# 12_BCKPLN_FPGA_J008340C.net
KiCad netlist of a schematic drawn in EAGLE
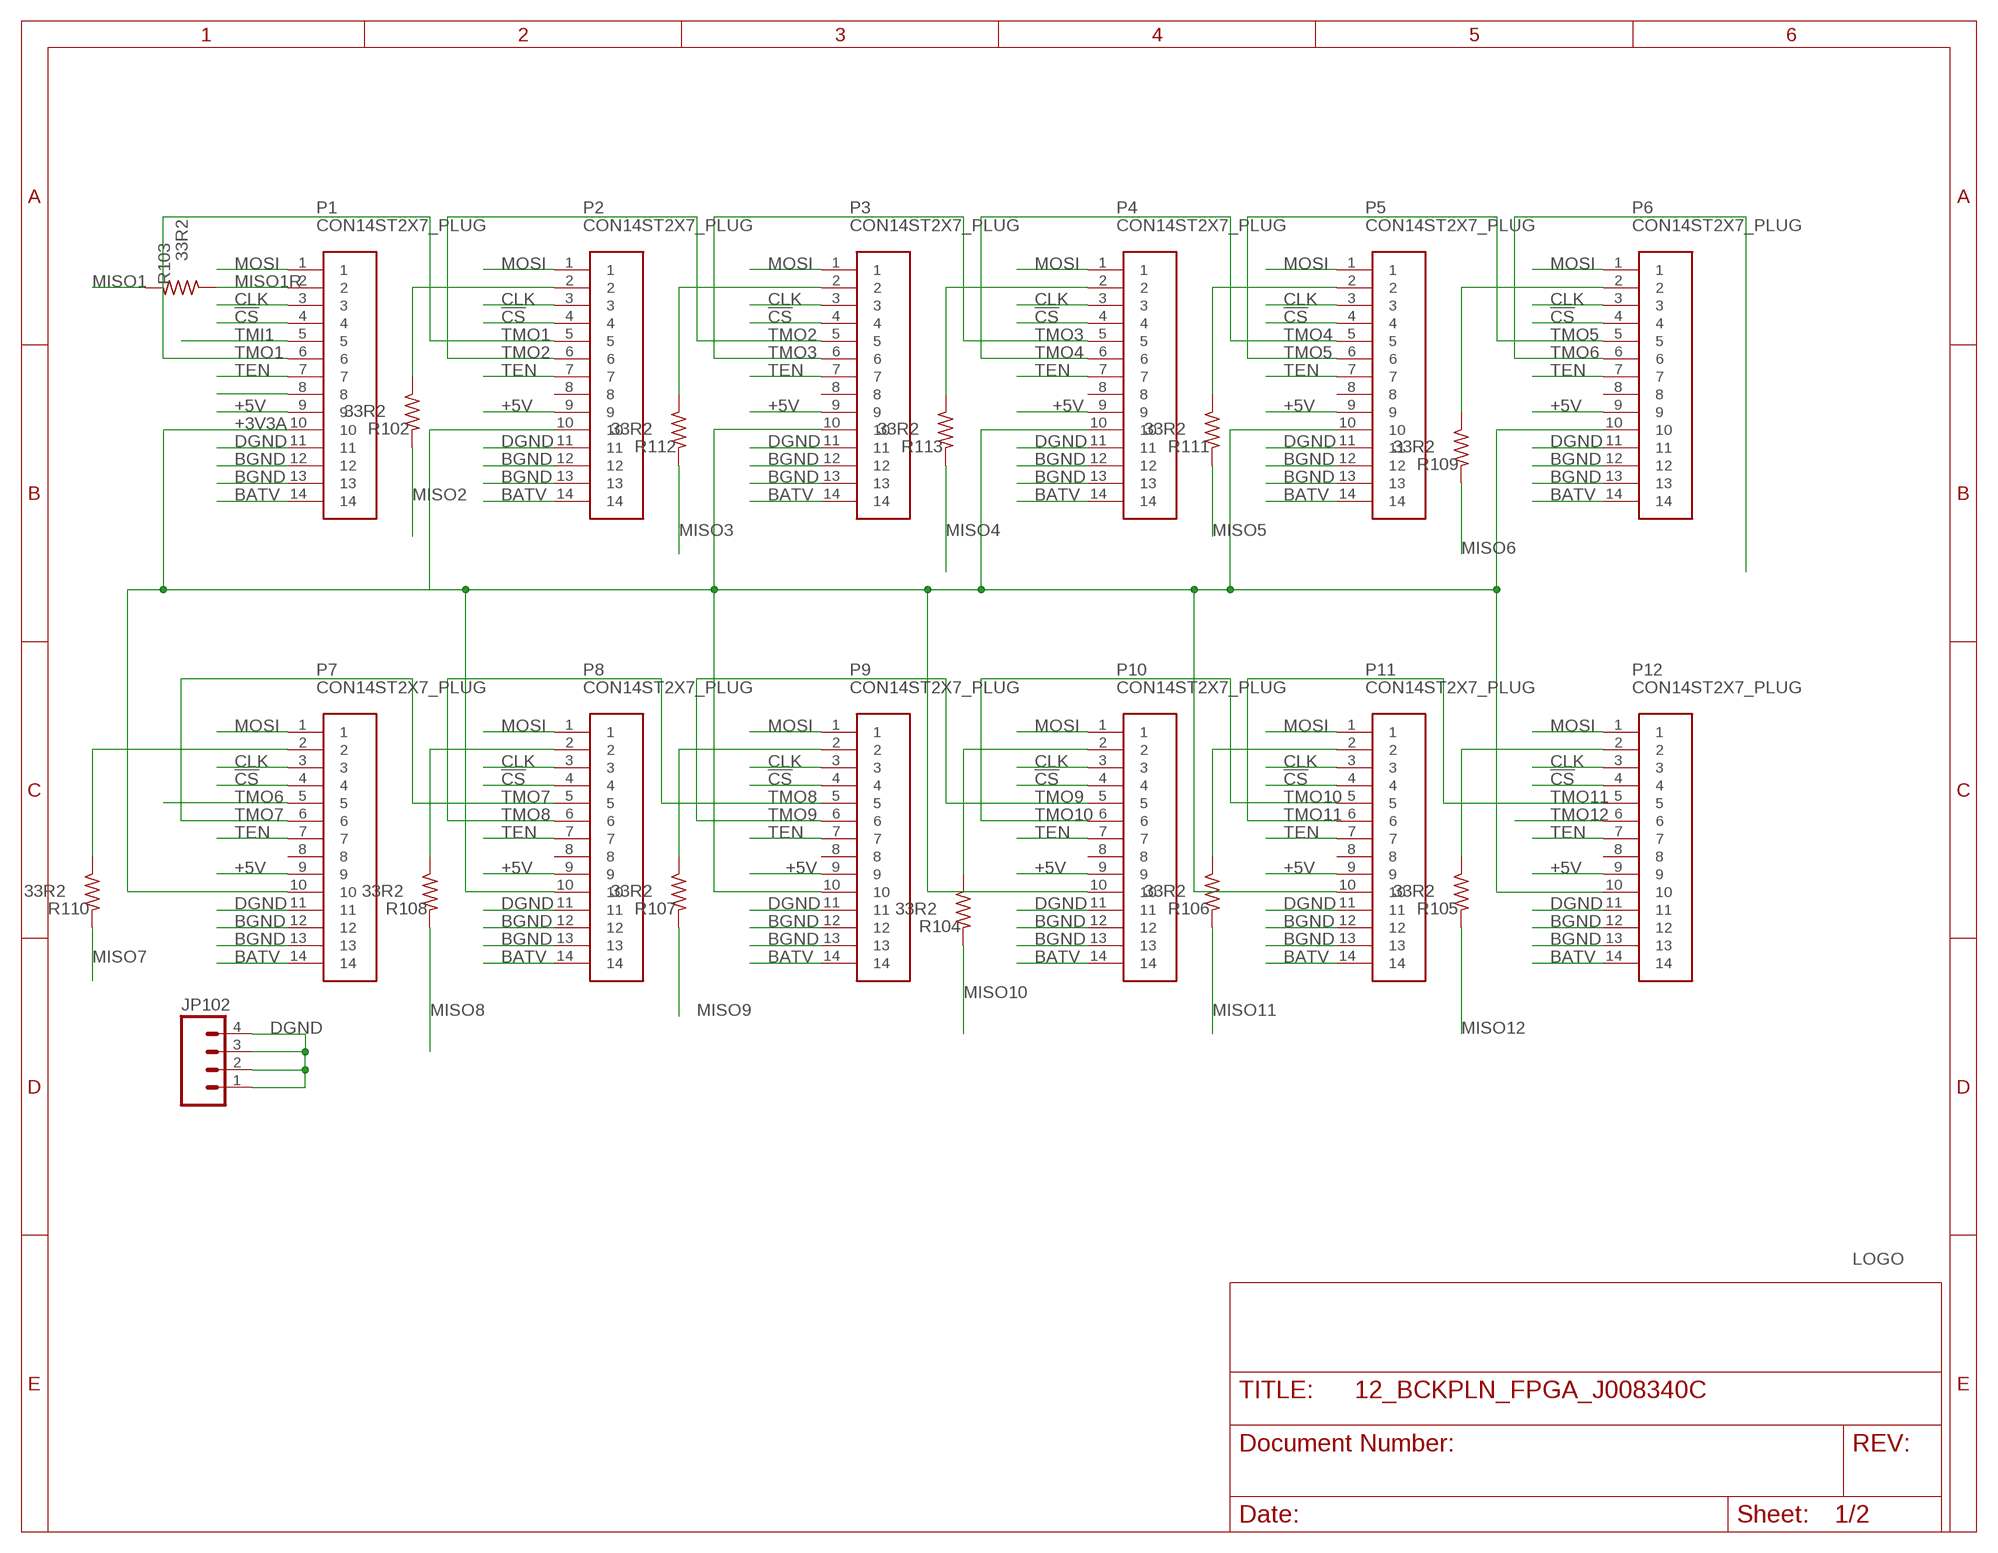
[diagram p0: schematic, sheet 1]
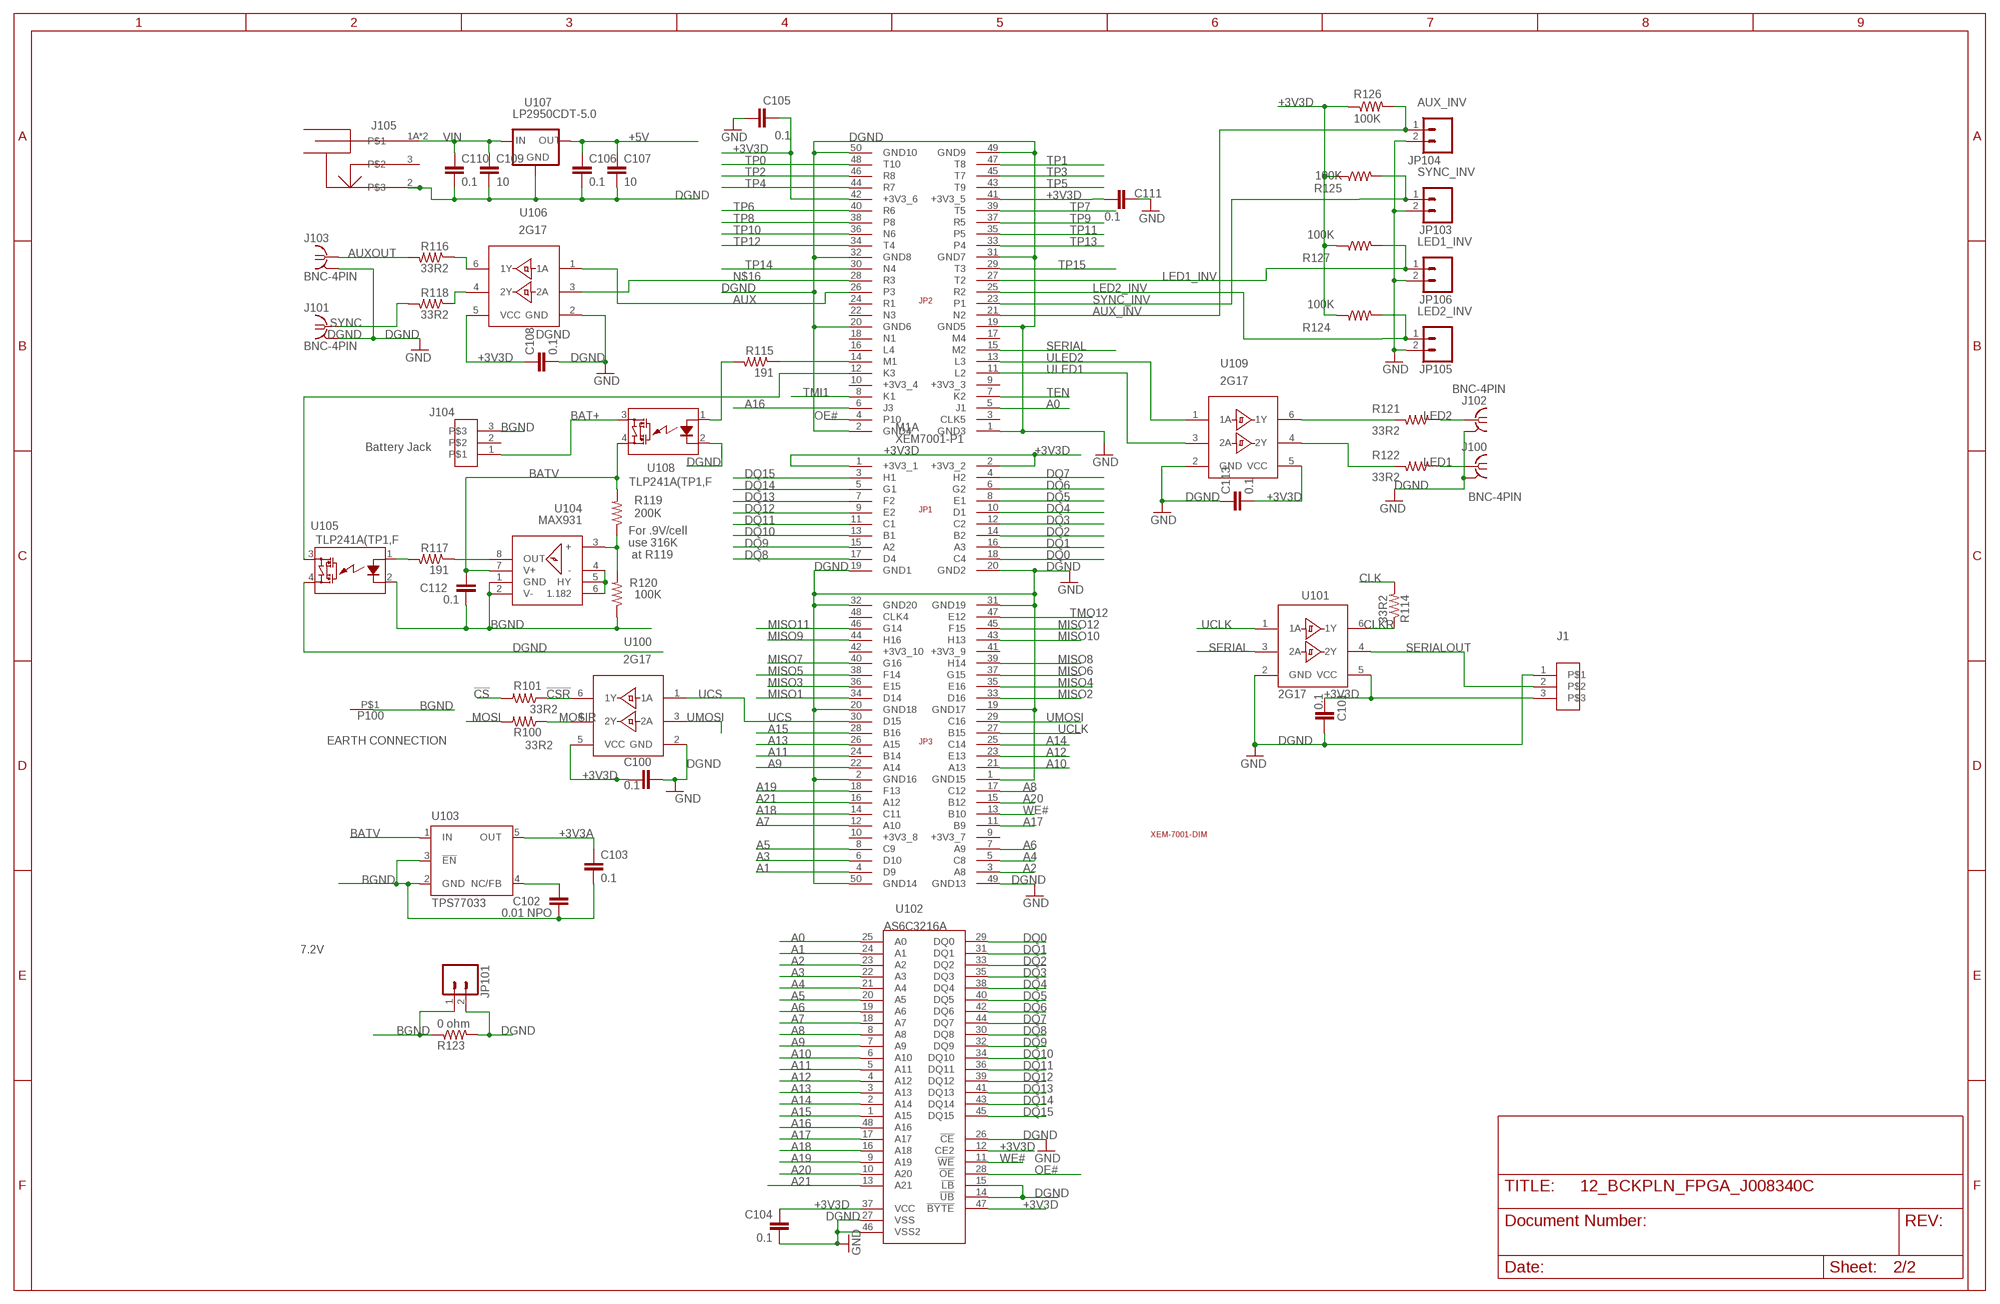
[diagram p1: schematic, sheet 2]

(export (version "E")
  (design (tool "Eeschema 10.0.6"))
  (components
    (comp (ref "C100")
      (value "0.1")
      (footprint "eagle-import:0603S")
      (libsource (lib "eagle-import") (part "CAPS0603S"))
    )
    (comp (ref "C101")
      (value "0.1")
      (footprint "eagle-import:0603S")
      (libsource (lib "eagle-import") (part "CAPS0603S"))
    )
    (comp (ref "C102")
      (value "0.01 NPO")
      (footprint "eagle-import:0805S")
      (libsource (lib "eagle-import") (part "CAPS0805S"))
    )
    (comp (ref "C103")
      (value "0.1")
      (footprint "eagle-import:0603S")
      (libsource (lib "eagle-import") (part "CAPS0603S"))
    )
    (comp (ref "C104")
      (value "0.1")
      (footprint "eagle-import:0603S")
      (libsource (lib "eagle-import") (part "CAPS0603S"))
    )
    (comp (ref "C105")
      (value "0.1")
      (footprint "eagle-import:0603S")
      (libsource (lib "eagle-import") (part "CAPS0603S"))
    )
    (comp (ref "C106")
      (value "0.1")
      (footprint "eagle-import:0603S")
      (libsource (lib "eagle-import") (part "CAPS0603S"))
    )
    (comp (ref "C107")
      (value "10")
      (footprint "eagle-import:1210S")
      (libsource (lib "eagle-import") (part "CAPS1210S"))
    )
    (comp (ref "C108")
      (value "0.1")
      (footprint "eagle-import:0603S")
      (libsource (lib "eagle-import") (part "CAPS0603S"))
    )
    (comp (ref "C109")
      (value "10")
      (footprint "eagle-import:1210S")
      (libsource (lib "eagle-import") (part "CAPS1210S"))
    )
    (comp (ref "C110")
      (value "0.1")
      (footprint "eagle-import:0603S")
      (libsource (lib "eagle-import") (part "CAPS0603S"))
    )
    (comp (ref "C111")
      (value "0.1")
      (footprint "eagle-import:0603S")
      (libsource (lib "eagle-import") (part "CAPS0603S"))
    )
    (comp (ref "C112")
      (value "0.1")
      (footprint "eagle-import:0603S")
      (libsource (lib "eagle-import") (part "CAPS0603S"))
    )
    (comp (ref "C113")
      (value "0.1")
      (footprint "eagle-import:0603S")
      (libsource (lib "eagle-import") (part "CAPS0603S"))
    )
    (comp (ref "J1")
      (value "CON3AMPMODU-3")
      (footprint "eagle-import:AMPMODU-3")
      (libsource (lib "eagle-import") (part "CON3AMPMODU-3"))
    )
    (comp (ref "J100")
      (value "BNC-4PIN")
      (footprint "eagle-import:BNC-4PIN")
      (libsource (lib "eagle-import") (part "BNCBNC-4PIN"))
    )
    (comp (ref "J101")
      (value "BNC-4PIN")
      (footprint "eagle-import:BNC-4PIN")
      (libsource (lib "eagle-import") (part "BNCBNC-4PIN"))
    )
    (comp (ref "J102")
      (value "BNC-4PIN")
      (footprint "eagle-import:BNC-4PIN")
      (libsource (lib "eagle-import") (part "BNCBNC-4PIN"))
    )
    (comp (ref "J103")
      (value "BNC-4PIN")
      (footprint "eagle-import:BNC-4PIN")
      (libsource (lib "eagle-import") (part "BNCBNC-4PIN"))
    )
    (comp (ref "J104")
      (value "Battery Jack")
      (footprint "eagle-import:975")
      (libsource (lib "eagle-import") (part "CON3975"))
    )
    (comp (ref "J105")
      (value "POWER_JACK_SHUNTPJ-002")
      (footprint "eagle-import:PJ-002")
      (libsource (lib "eagle-import") (part "POWER_JACK_SHUNTPJ-002"))
    )
    (comp (ref "JP101")
      (value "M02LOCK")
      (footprint "eagle-import:1X02_LOCK")
      (libsource (lib "eagle-import") (part "M02LOCK"))
    )
    (comp (ref "JP103")
      (value "M02LOCK")
      (footprint "eagle-import:1X02_LOCK")
      (libsource (lib "eagle-import") (part "M02LOCK"))
    )
    (comp (ref "JP104")
      (value "M02LOCK")
      (footprint "eagle-import:1X02_LOCK")
      (libsource (lib "eagle-import") (part "M02LOCK"))
    )
    (comp (ref "JP105")
      (value "M02LOCK")
      (footprint "eagle-import:1X02_LOCK")
      (libsource (lib "eagle-import") (part "M02LOCK"))
    )
    (comp (ref "JP106")
      (value "M02LOCK")
      (footprint "eagle-import:1X02_LOCK")
      (libsource (lib "eagle-import") (part "M02LOCK"))
    )
    (comp (ref "M1")
      (value "XEM7001-OUTLINE")
      (footprint "eagle-import:XEM7001-OUTLINE")
      (libsource (lib "eagle-import") (part "XEM7001-OUTLINE"))
    )
    (comp (ref "M1A")
      (value "XEM7001-P1")
      (footprint "eagle-import:2X10")
      (libsource (lib "eagle-import") (part "XEM7001-P1"))
    )
    (comp (ref "M1B")
      (value "XEM7001-P2")
      (footprint "eagle-import:2X25")
      (libsource (lib "eagle-import") (part "XEM7001-P2"))
    )
    (comp (ref "M1C")
      (value "XEM7001-P3")
      (footprint "eagle-import:2X25")
      (libsource (lib "eagle-import") (part "XEM7001-P3"))
    )
    (comp (ref "P100")
      (value "CON1BANANA-1")
      (footprint "eagle-import:BANANA-1")
      (libsource (lib "eagle-import") (part "CON1BANANA-1"))
    )
    (comp (ref "R100")
      (value "33R2")
      (footprint "eagle-import:0805S")
      (libsource (lib "eagle-import") (part "STEVES_BU_RESISTOR_SM0805S"))
    )
    (comp (ref "R101")
      (value "33R2")
      (footprint "eagle-import:0805S")
      (libsource (lib "eagle-import") (part "STEVES_BU_RESISTOR_SM0805S"))
    )
    (comp (ref "R114")
      (value "33R2")
      (footprint "eagle-import:0805S")
      (libsource (lib "eagle-import") (part "STEVES_BU_RESISTOR_SM0805S"))
    )
    (comp (ref "R115")
      (value "191")
      (footprint "eagle-import:0805S")
      (libsource (lib "eagle-import") (part "STEVES_BU_RESISTOR_SM0805S"))
    )
    (comp (ref "R116")
      (value "33R2")
      (footprint "eagle-import:0805S")
      (libsource (lib "eagle-import") (part "RESISTOR_SM0805S"))
    )
    (comp (ref "R117")
      (value "191")
      (footprint "eagle-import:0805S")
      (libsource (lib "eagle-import") (part "STEVES_BU_RESISTOR_SM0805S"))
    )
    (comp (ref "R118")
      (value "33R2")
      (footprint "eagle-import:0805S")
      (libsource (lib "eagle-import") (part "RESISTOR_SM0805S"))
    )
    (comp (ref "R119")
      (value "200K")
      (footprint "eagle-import:0805S")
      (libsource (lib "eagle-import") (part "STEVES_BU_RESISTOR_SM0805S"))
    )
    (comp (ref "R120")
      (value "100K")
      (footprint "eagle-import:0805S")
      (libsource (lib "eagle-import") (part "STEVES_BU_RESISTOR_SM0805S"))
    )
    (comp (ref "R121")
      (value "33R2")
      (footprint "eagle-import:0805S")
      (libsource (lib "eagle-import") (part "RESISTOR_SM0805S"))
    )
    (comp (ref "R122")
      (value "33R2")
      (footprint "eagle-import:0805S")
      (libsource (lib "eagle-import") (part "RESISTOR_SM0805S"))
    )
    (comp (ref "R123")
      (value "0 ohm")
      (footprint "eagle-import:0805S")
      (libsource (lib "eagle-import") (part "STEVES_BU_RESISTOR_SM0805S"))
    )
    (comp (ref "R124")
      (value "100K")
      (footprint "eagle-import:0805S")
      (libsource (lib "eagle-import") (part "STEVES_BU_RESISTOR_SM0805S"))
    )
    (comp (ref "R125")
      (value "100K")
      (footprint "eagle-import:0805S")
      (libsource (lib "eagle-import") (part "STEVES_BU_RESISTOR_SM0805S"))
    )
    (comp (ref "R126")
      (value "100K")
      (footprint "eagle-import:0805S")
      (libsource (lib "eagle-import") (part "STEVES_BU_RESISTOR_SM0805S"))
    )
    (comp (ref "R127")
      (value "100K")
      (footprint "eagle-import:0805S")
      (libsource (lib "eagle-import") (part "STEVES_BU_RESISTOR_SM0805S"))
    )
    (comp (ref "U100")
      (value "2G17")
      (footprint "eagle-import:SOT23-6")
      (libsource (lib "eagle-import") (part "2G17"))
    )
    (comp (ref "U101")
      (value "2G17")
      (footprint "eagle-import:SOT23-6")
      (libsource (lib "eagle-import") (part "2G17"))
    )
    (comp (ref "U102")
      (value "AS6C3216A")
      (footprint "eagle-import:TSSOP48-12X20")
      (libsource (lib "eagle-import") (part "AS6C3216A"))
    )
    (comp (ref "U103")
      (value "TPS77033")
      (footprint "eagle-import:SOT23-DBV")
      (fields (field (name "MF") "TEXAS INSTRUMENTS") (field (name "MPN") "TPS77033DBVT"))
      (libsource (lib "eagle-import") (part "TPS77033"))
    )
    (comp (ref "U104")
      (value "MAX931")
      (footprint "eagle-import:SOIC8")
      (libsource (lib "eagle-import") (part "MAX931"))
    )
    (comp (ref "U105")
      (value "TLP241A(TP1,F")
      (footprint "eagle-import:SMD4-GULL")
      (libsource (lib "eagle-import") (part "RELAY_SSRSMD4-GULL"))
    )
    (comp (ref "U106")
      (value "2G17")
      (footprint "eagle-import:SOT23-6")
      (libsource (lib "eagle-import") (part "2G17"))
    )
    (comp (ref "U107")
      (value "LP2950CDT-5.0")
      (footprint "eagle-import:DPACK")
      (libsource (lib "eagle-import") (part "LP2950?CDT-5.0"))
    )
    (comp (ref "U108")
      (value "TLP241A(TP1,F")
      (footprint "eagle-import:SMD4-GULL")
      (libsource (lib "eagle-import") (part "RELAY_SSRSMD4-GULL"))
    )
    (comp (ref "U109")
      (value "2G17")
      (footprint "eagle-import:SOT23-6")
      (libsource (lib "eagle-import") (part "2G17"))
    )
    (comp (ref "JP102")
      (value "M04LOCK")
      (footprint "eagle-import:1X04_LOCK")
      (libsource (lib "eagle-import") (part "M04LOCK"))
    )
    (comp (ref "P1")
      (value "CON14ST2X7_PLUG")
      (footprint "eagle-import:2X7_PLUG")
      (libsource (lib "eagle-import") (part "CON14ST2X7_PLUG"))
    )
    (comp (ref "P2")
      (value "CON14ST2X7_PLUG")
      (footprint "eagle-import:2X7_PLUG")
      (libsource (lib "eagle-import") (part "CON14ST2X7_PLUG"))
    )
    (comp (ref "P3")
      (value "CON14ST2X7_PLUG")
      (footprint "eagle-import:2X7_PLUG")
      (libsource (lib "eagle-import") (part "CON14ST2X7_PLUG"))
    )
    (comp (ref "P4")
      (value "CON14ST2X7_PLUG")
      (footprint "eagle-import:2X7_PLUG")
      (libsource (lib "eagle-import") (part "CON14ST2X7_PLUG"))
    )
    (comp (ref "P5")
      (value "CON14ST2X7_PLUG")
      (footprint "eagle-import:2X7_PLUG")
      (libsource (lib "eagle-import") (part "CON14ST2X7_PLUG"))
    )
    (comp (ref "P6")
      (value "CON14ST2X7_PLUG")
      (footprint "eagle-import:2X7_PLUG")
      (libsource (lib "eagle-import") (part "CON14ST2X7_PLUG"))
    )
    (comp (ref "P7")
      (value "CON14ST2X7_PLUG")
      (footprint "eagle-import:2X7_PLUG")
      (libsource (lib "eagle-import") (part "CON14ST2X7_PLUG"))
    )
    (comp (ref "P8")
      (value "CON14ST2X7_PLUG")
      (footprint "eagle-import:2X7_PLUG")
      (libsource (lib "eagle-import") (part "CON14ST2X7_PLUG"))
    )
    (comp (ref "P9")
      (value "CON14ST2X7_PLUG")
      (footprint "eagle-import:2X7_PLUG")
      (libsource (lib "eagle-import") (part "CON14ST2X7_PLUG"))
    )
    (comp (ref "P10")
      (value "CON14ST2X7_PLUG")
      (footprint "eagle-import:2X7_PLUG")
      (libsource (lib "eagle-import") (part "CON14ST2X7_PLUG"))
    )
    (comp (ref "P11")
      (value "CON14ST2X7_PLUG")
      (footprint "eagle-import:2X7_PLUG")
      (libsource (lib "eagle-import") (part "CON14ST2X7_PLUG"))
    )
    (comp (ref "P12")
      (value "CON14ST2X7_PLUG")
      (footprint "eagle-import:2X7_PLUG")
      (libsource (lib "eagle-import") (part "CON14ST2X7_PLUG"))
    )
    (comp (ref "R102")
      (value "33R2")
      (footprint "eagle-import:0805S")
      (libsource (lib "eagle-import") (part "STEVES_BU_RESISTOR_SM0805S"))
    )
    (comp (ref "R103")
      (value "33R2")
      (footprint "eagle-import:0805S")
      (libsource (lib "eagle-import") (part "STEVES_BU_RESISTOR_SM0805S"))
    )
    (comp (ref "R104")
      (value "33R2")
      (footprint "eagle-import:0805S")
      (libsource (lib "eagle-import") (part "STEVES_BU_RESISTOR_SM0805S"))
    )
    (comp (ref "R105")
      (value "33R2")
      (footprint "eagle-import:0805S")
      (libsource (lib "eagle-import") (part "STEVES_BU_RESISTOR_SM0805S"))
    )
    (comp (ref "R106")
      (value "33R2")
      (footprint "eagle-import:0805S")
      (libsource (lib "eagle-import") (part "STEVES_BU_RESISTOR_SM0805S"))
    )
    (comp (ref "R107")
      (value "33R2")
      (footprint "eagle-import:0805S")
      (libsource (lib "eagle-import") (part "STEVES_BU_RESISTOR_SM0805S"))
    )
    (comp (ref "R108")
      (value "33R2")
      (footprint "eagle-import:0805S")
      (libsource (lib "eagle-import") (part "STEVES_BU_RESISTOR_SM0805S"))
    )
    (comp (ref "R109")
      (value "33R2")
      (footprint "eagle-import:0805S")
      (libsource (lib "eagle-import") (part "STEVES_BU_RESISTOR_SM0805S"))
    )
    (comp (ref "R110")
      (value "33R2")
      (footprint "eagle-import:0805S")
      (libsource (lib "eagle-import") (part "STEVES_BU_RESISTOR_SM0805S"))
    )
    (comp (ref "R111")
      (value "33R2")
      (footprint "eagle-import:0805S")
      (libsource (lib "eagle-import") (part "STEVES_BU_RESISTOR_SM0805S"))
    )
    (comp (ref "R112")
      (value "33R2")
      (footprint "eagle-import:0805S")
      (libsource (lib "eagle-import") (part "STEVES_BU_RESISTOR_SM0805S"))
    )
    (comp (ref "R113")
      (value "33R2")
      (footprint "eagle-import:0805S")
      (libsource (lib "eagle-import") (part "STEVES_BU_RESISTOR_SM0805S"))
    )
    (comp (ref "U$1")
      (value "JFRC-LOGOLOGO_OP")
      (footprint "eagle-import:LOGO_BMP_OP")
      (libsource (lib "eagle-import") (part "JFRC-LOGOLOGO_OP"))
    )
  )
  (nets
    (net (code "1") (name "+3V3A") (class "Default")
      (node (ref "C103") (pin "1") (pinfunction "1_1") (pintype "passive"))
      (node (ref "P1") (pin "10") (pinfunction "10_10") (pintype "bidirectional"))
      (node (ref "P10") (pin "10") (pinfunction "10_10") (pintype "bidirectional"))
      (node (ref "P11") (pin "10") (pinfunction "10_10") (pintype "bidirectional"))
      (node (ref "P12") (pin "10") (pinfunction "10_10") (pintype "bidirectional"))
      (node (ref "P2") (pin "10") (pinfunction "10_10") (pintype "bidirectional"))
      (node (ref "P3") (pin "10") (pinfunction "10_10") (pintype "bidirectional"))
      (node (ref "P4") (pin "10") (pinfunction "10_10") (pintype "bidirectional"))
      (node (ref "P5") (pin "10") (pinfunction "10_10") (pintype "bidirectional"))
      (node (ref "P6") (pin "10") (pinfunction "10_10") (pintype "bidirectional"))
      (node (ref "P7") (pin "10") (pinfunction "10_10") (pintype "bidirectional"))
      (node (ref "P8") (pin "10") (pinfunction "10_10") (pintype "bidirectional"))
      (node (ref "P9") (pin "10") (pinfunction "10_10") (pintype "bidirectional"))
      (node (ref "U103") (pin "5") (pinfunction "OUT_5") (pintype "passive"))
    )
    (net (code "2") (name "+3V3D") (class "Default")
      (node (ref "C100") (pin "1") (pinfunction "1_1") (pintype "passive"))
      (node (ref "C101") (pin "1") (pinfunction "1_1") (pintype "passive"))
      (node (ref "C104") (pin "1") (pinfunction "1_1") (pintype "passive"))
      (node (ref "C105") (pin "1") (pinfunction "1_1") (pintype "passive"))
      (node (ref "C108") (pin "1") (pinfunction "1_1") (pintype "passive"))
      (node (ref "C111") (pin "1") (pinfunction "1_1") (pintype "passive"))
      (node (ref "C113") (pin "2") (pinfunction "2_2") (pintype "passive"))
      (node (ref "J1") (pin "3") (pinfunction "P$3_3") (pintype "bidirectional"))
      (node (ref "M1A") (pin "1") (pinfunction "+3V3_1_1") (pintype "bidirectional"))
      (node (ref "M1A") (pin "2") (pinfunction "+3V3_2_2") (pintype "bidirectional"))
      (node (ref "M1B") (pin "41") (pinfunction "+3V3_5_41") (pintype "bidirectional"))
      (node (ref "M1B") (pin "42") (pinfunction "+3V3_6_42") (pintype "bidirectional"))
      (node (ref "R124") (pin "1") (pinfunction "1_1") (pintype "passive"))
      (node (ref "R125") (pin "1") (pinfunction "1_1") (pintype "passive"))
      (node (ref "R126") (pin "1") (pinfunction "1_1") (pintype "passive"))
      (node (ref "R127") (pin "1") (pinfunction "1_1") (pintype "passive"))
      (node (ref "U100") (pin "5") (pinfunction "VCC_5") (pintype "bidirectional"))
      (node (ref "U101") (pin "5") (pinfunction "VCC_5") (pintype "bidirectional"))
      (node (ref "U102") (pin "12") (pinfunction "CE2_12") (pintype "bidirectional"))
      (node (ref "U102") (pin "37") (pinfunction "VCC_37") (pintype "bidirectional"))
      (node (ref "U102") (pin "47") (pinfunction "~{BYTE}_47") (pintype "bidirectional"))
      (node (ref "U106") (pin "5") (pinfunction "VCC_5") (pintype "bidirectional"))
      (node (ref "U109") (pin "5") (pinfunction "VCC_5") (pintype "bidirectional"))
    )
    (net (code "3") (name "+5V") (class "Default")
      (node (ref "C106") (pin "1") (pinfunction "1_1") (pintype "passive"))
      (node (ref "C107") (pin "1") (pinfunction "1_1") (pintype "passive"))
      (node (ref "P1") (pin "9") (pinfunction "9_9") (pintype "bidirectional"))
      (node (ref "P10") (pin "9") (pinfunction "9_9") (pintype "bidirectional"))
      (node (ref "P11") (pin "9") (pinfunction "9_9") (pintype "bidirectional"))
      (node (ref "P12") (pin "9") (pinfunction "9_9") (pintype "bidirectional"))
      (node (ref "P2") (pin "9") (pinfunction "9_9") (pintype "bidirectional"))
      (node (ref "P3") (pin "9") (pinfunction "9_9") (pintype "bidirectional"))
      (node (ref "P4") (pin "9") (pinfunction "9_9") (pintype "bidirectional"))
      (node (ref "P5") (pin "9") (pinfunction "9_9") (pintype "bidirectional"))
      (node (ref "P6") (pin "9") (pinfunction "9_9") (pintype "bidirectional"))
      (node (ref "P7") (pin "9") (pinfunction "9_9") (pintype "bidirectional"))
      (node (ref "P8") (pin "9") (pinfunction "9_9") (pintype "bidirectional"))
      (node (ref "P9") (pin "9") (pinfunction "9_9") (pintype "bidirectional"))
      (node (ref "U107") (pin "3") (pinfunction "OUT_3") (pintype "passive"))
    )
    (net (code "4") (name "A0") (class "Default")
      (node (ref "M1B") (pin "5") (pinfunction "J1_5") (pintype "bidirectional"))
      (node (ref "U102") (pin "25") (pinfunction "A0_25") (pintype "bidirectional"))
    )
    (net (code "5") (name "A1") (class "Default")
      (node (ref "M1C") (pin "4") (pinfunction "D9_4") (pintype "bidirectional"))
      (node (ref "U102") (pin "24") (pinfunction "A1_24") (pintype "bidirectional"))
    )
    (net (code "6") (name "A2") (class "Default")
      (node (ref "M1C") (pin "3") (pinfunction "A8_3") (pintype "bidirectional"))
      (node (ref "U102") (pin "23") (pinfunction "A2_23") (pintype "bidirectional"))
    )
    (net (code "7") (name "A3") (class "Default")
      (node (ref "M1C") (pin "6") (pinfunction "D10_6") (pintype "bidirectional"))
      (node (ref "U102") (pin "22") (pinfunction "A3_22") (pintype "bidirectional"))
    )
    (net (code "8") (name "A4") (class "Default")
      (node (ref "M1C") (pin "5") (pinfunction "C8_5") (pintype "bidirectional"))
      (node (ref "U102") (pin "21") (pinfunction "A4_21") (pintype "bidirectional"))
    )
    (net (code "9") (name "A5") (class "Default")
      (node (ref "M1C") (pin "8") (pinfunction "C9_8") (pintype "bidirectional"))
      (node (ref "U102") (pin "20") (pinfunction "A5_20") (pintype "bidirectional"))
    )
    (net (code "10") (name "A6") (class "Default")
      (node (ref "M1C") (pin "7") (pinfunction "A9_7") (pintype "bidirectional"))
      (node (ref "U102") (pin "19") (pinfunction "A6_19") (pintype "bidirectional"))
    )
    (net (code "11") (name "A7") (class "Default")
      (node (ref "M1C") (pin "12") (pinfunction "A10_12") (pintype "bidirectional"))
      (node (ref "U102") (pin "18") (pinfunction "A7_18") (pintype "bidirectional"))
    )
    (net (code "12") (name "A8") (class "Default")
      (node (ref "M1C") (pin "17") (pinfunction "C12_17") (pintype "bidirectional"))
      (node (ref "U102") (pin "8") (pinfunction "A8_8") (pintype "bidirectional"))
    )
    (net (code "13") (name "A9") (class "Default")
      (node (ref "M1C") (pin "22") (pinfunction "A14_22") (pintype "bidirectional"))
      (node (ref "U102") (pin "7") (pinfunction "A9_7") (pintype "bidirectional"))
    )
    (net (code "14") (name "A10") (class "Default")
      (node (ref "M1C") (pin "21") (pinfunction "A13_21") (pintype "bidirectional"))
      (node (ref "U102") (pin "6") (pinfunction "A10_6") (pintype "bidirectional"))
    )
    (net (code "15") (name "A11") (class "Default")
      (node (ref "M1C") (pin "24") (pinfunction "B14_24") (pintype "bidirectional"))
      (node (ref "U102") (pin "5") (pinfunction "A11_5") (pintype "bidirectional"))
    )
    (net (code "16") (name "A12") (class "Default")
      (node (ref "M1C") (pin "23") (pinfunction "E13_23") (pintype "bidirectional"))
      (node (ref "U102") (pin "4") (pinfunction "A12_4") (pintype "bidirectional"))
    )
    (net (code "17") (name "A13") (class "Default")
      (node (ref "M1C") (pin "26") (pinfunction "A15_26") (pintype "bidirectional"))
      (node (ref "U102") (pin "3") (pinfunction "A13_3") (pintype "bidirectional"))
    )
    (net (code "18") (name "A14") (class "Default")
      (node (ref "M1C") (pin "25") (pinfunction "C14_25") (pintype "bidirectional"))
      (node (ref "U102") (pin "2") (pinfunction "A14_2") (pintype "bidirectional"))
    )
    (net (code "19") (name "A15") (class "Default")
      (node (ref "M1C") (pin "28") (pinfunction "B16_28") (pintype "bidirectional"))
      (node (ref "U102") (pin "1") (pinfunction "A15_1") (pintype "bidirectional"))
    )
    (net (code "20") (name "A16") (class "Default")
      (node (ref "M1B") (pin "6") (pinfunction "J3_6") (pintype "bidirectional"))
      (node (ref "U102") (pin "48") (pinfunction "A16_48") (pintype "bidirectional"))
    )
    (net (code "21") (name "A17") (class "Default")
      (node (ref "M1C") (pin "11") (pinfunction "B9_11") (pintype "bidirectional"))
      (node (ref "U102") (pin "17") (pinfunction "A17_17") (pintype "bidirectional"))
    )
    (net (code "22") (name "A18") (class "Default")
      (node (ref "M1C") (pin "14") (pinfunction "C11_14") (pintype "bidirectional"))
      (node (ref "U102") (pin "16") (pinfunction "A18_16") (pintype "bidirectional"))
    )
    (net (code "23") (name "A19") (class "Default")
      (node (ref "M1C") (pin "18") (pinfunction "F13_18") (pintype "bidirectional"))
      (node (ref "U102") (pin "9") (pinfunction "A19_9") (pintype "bidirectional"))
    )
    (net (code "24") (name "A20") (class "Default")
      (node (ref "M1C") (pin "15") (pinfunction "B12_15") (pintype "bidirectional"))
      (node (ref "U102") (pin "10") (pinfunction "A20_10") (pintype "bidirectional"))
    )
    (net (code "25") (name "A21") (class "Default")
      (node (ref "M1C") (pin "16") (pinfunction "A12_16") (pintype "bidirectional"))
      (node (ref "U102") (pin "13") (pinfunction "A21_13") (pintype "bidirectional"))
    )
    (net (code "26") (name "AUX") (class "Default")
      (node (ref "M1B") (pin "26") (pinfunction "P3_26") (pintype "bidirectional"))
      (node (ref "U106") (pin "1") (pinfunction "1A_1") (pintype "bidirectional"))
    )
    (net (code "27") (name "AUXOUT") (class "Default")
      (node (ref "J103") (pin "S") (pinfunction "1_S") (pintype "passive"))
      (node (ref "R116") (pin "2") (pinfunction "2_2") (pintype "passive"))
    )
    (net (code "28") (name "AUX_INV") (class "Default")
      (node (ref "JP104") (pin "1") (pinfunction "1_1") (pintype "passive"))
      (node (ref "M1B") (pin "21") (pinfunction "N2_21") (pintype "bidirectional"))
      (node (ref "R126") (pin "2") (pinfunction "2_2") (pintype "passive"))
    )
    (net (code "29") (name "BAT+") (class "Default")
      (node (ref "J104") (pin "1") (pinfunction "P$1_1") (pintype "bidirectional"))
      (node (ref "U108") (pin "3") (pinfunction "DS1_3") (pintype "passive"))
    )
    (net (code "30") (name "BATV") (class "Default")
      (node (ref "C112") (pin "1") (pinfunction "1_1") (pintype "passive"))
      (node (ref "P1") (pin "14") (pinfunction "14_14") (pintype "bidirectional"))
      (node (ref "P10") (pin "14") (pinfunction "14_14") (pintype "bidirectional"))
      (node (ref "P11") (pin "14") (pinfunction "14_14") (pintype "bidirectional"))
      (node (ref "P12") (pin "14") (pinfunction "14_14") (pintype "bidirectional"))
      (node (ref "P2") (pin "14") (pinfunction "14_14") (pintype "bidirectional"))
      (node (ref "P3") (pin "14") (pinfunction "14_14") (pintype "bidirectional"))
      (node (ref "P4") (pin "14") (pinfunction "14_14") (pintype "bidirectional"))
      (node (ref "P5") (pin "14") (pinfunction "14_14") (pintype "bidirectional"))
      (node (ref "P6") (pin "14") (pinfunction "14_14") (pintype "bidirectional"))
      (node (ref "P7") (pin "14") (pinfunction "14_14") (pintype "bidirectional"))
      (node (ref "P8") (pin "14") (pinfunction "14_14") (pintype "bidirectional"))
      (node (ref "P9") (pin "14") (pinfunction "14_14") (pintype "bidirectional"))
      (node (ref "R119") (pin "2") (pinfunction "2_2") (pintype "passive"))
      (node (ref "U103") (pin "1") (pinfunction "IN_1") (pintype "input"))
      (node (ref "U104") (pin "7") (pinfunction "V+_7") (pintype "bidirectional"))
      (node (ref "U108") (pin "4") (pinfunction "DS2_4") (pintype "passive"))
    )
    (net (code "31") (name "BGND") (class "Default")
      (node (ref "C102") (pin "2") (pinfunction "2_2") (pintype "passive"))
      (node (ref "C103") (pin "2") (pinfunction "2_2") (pintype "passive"))
      (node (ref "C112") (pin "2") (pinfunction "2_2") (pintype "passive"))
      (node (ref "J104") (pin "3") (pinfunction "P$3_3") (pintype "bidirectional"))
      (node (ref "JP101") (pin "1") (pinfunction "1_1") (pintype "passive"))
      (node (ref "P1") (pin "12") (pinfunction "12_12") (pintype "bidirectional"))
      (node (ref "P1") (pin "13") (pinfunction "13_13") (pintype "bidirectional"))
      (node (ref "P10") (pin "12") (pinfunction "12_12") (pintype "bidirectional"))
      (node (ref "P10") (pin "13") (pinfunction "13_13") (pintype "bidirectional"))
      (node (ref "P100") (pin "P$1") (pinfunction "1_P$1") (pintype "bidirectional"))
      (node (ref "P11") (pin "12") (pinfunction "12_12") (pintype "bidirectional"))
      (node (ref "P11") (pin "13") (pinfunction "13_13") (pintype "bidirectional"))
      (node (ref "P12") (pin "12") (pinfunction "12_12") (pintype "bidirectional"))
      (node (ref "P12") (pin "13") (pinfunction "13_13") (pintype "bidirectional"))
      (node (ref "P2") (pin "12") (pinfunction "12_12") (pintype "bidirectional"))
      (node (ref "P2") (pin "13") (pinfunction "13_13") (pintype "bidirectional"))
      (node (ref "P3") (pin "12") (pinfunction "12_12") (pintype "bidirectional"))
      (node (ref "P3") (pin "13") (pinfunction "13_13") (pintype "bidirectional"))
      (node (ref "P4") (pin "12") (pinfunction "12_12") (pintype "bidirectional"))
      (node (ref "P4") (pin "13") (pinfunction "13_13") (pintype "bidirectional"))
      (node (ref "P5") (pin "12") (pinfunction "12_12") (pintype "bidirectional"))
      (node (ref "P5") (pin "13") (pinfunction "13_13") (pintype "bidirectional"))
      (node (ref "P6") (pin "12") (pinfunction "12_12") (pintype "bidirectional"))
      (node (ref "P6") (pin "13") (pinfunction "13_13") (pintype "bidirectional"))
      (node (ref "P7") (pin "12") (pinfunction "12_12") (pintype "bidirectional"))
      (node (ref "P7") (pin "13") (pinfunction "13_13") (pintype "bidirectional"))
      (node (ref "P8") (pin "12") (pinfunction "12_12") (pintype "bidirectional"))
      (node (ref "P8") (pin "13") (pinfunction "13_13") (pintype "bidirectional"))
      (node (ref "P9") (pin "12") (pinfunction "12_12") (pintype "bidirectional"))
      (node (ref "P9") (pin "13") (pinfunction "13_13") (pintype "bidirectional"))
      (node (ref "R120") (pin "1") (pinfunction "1_1") (pintype "passive"))
      (node (ref "R123") (pin "1") (pinfunction "1_1") (pintype "passive"))
      (node (ref "U103") (pin "2") (pinfunction "GND_2") (pintype "power_in"))
      (node (ref "U103") (pin "3") (pinfunction "~{EN}_3") (pintype "input"))
      (node (ref "U104") (pin "1") (pinfunction "GND_1") (pintype "bidirectional"))
      (node (ref "U104") (pin "2") (pinfunction "V-_2") (pintype "bidirectional"))
      (node (ref "U105") (pin "2") (pinfunction "K_2") (pintype "passive"))
    )
    (net (code "32") (name "CLK") (class "Default")
      (node (ref "P1") (pin "3") (pinfunction "3_3") (pintype "bidirectional"))
      (node (ref "P10") (pin "3") (pinfunction "3_3") (pintype "bidirectional"))
      (node (ref "P11") (pin "3") (pinfunction "3_3") (pintype "bidirectional"))
      (node (ref "P12") (pin "3") (pinfunction "3_3") (pintype "bidirectional"))
      (node (ref "P2") (pin "3") (pinfunction "3_3") (pintype "bidirectional"))
      (node (ref "P3") (pin "3") (pinfunction "3_3") (pintype "bidirectional"))
      (node (ref "P4") (pin "3") (pinfunction "3_3") (pintype "bidirectional"))
      (node (ref "P5") (pin "3") (pinfunction "3_3") (pintype "bidirectional"))
      (node (ref "P6") (pin "3") (pinfunction "3_3") (pintype "bidirectional"))
      (node (ref "P7") (pin "3") (pinfunction "3_3") (pintype "bidirectional"))
      (node (ref "P8") (pin "3") (pinfunction "3_3") (pintype "bidirectional"))
      (node (ref "P9") (pin "3") (pinfunction "3_3") (pintype "bidirectional"))
      (node (ref "R114") (pin "2") (pinfunction "2_2") (pintype "passive"))
    )
    (net (code "33") (name "CLKR") (class "Default")
      (node (ref "R114") (pin "1") (pinfunction "1_1") (pintype "passive"))
      (node (ref "U101") (pin "6") (pinfunction "1Y_6") (pintype "bidirectional"))
    )
    (net (code "34") (name "DGND") (class "Default")
      (node (ref "C100") (pin "2") (pinfunction "2_2") (pintype "passive"))
      (node (ref "C101") (pin "2") (pinfunction "2_2") (pintype "passive"))
      (node (ref "C104") (pin "2") (pinfunction "2_2") (pintype "passive"))
      (node (ref "C105") (pin "2") (pinfunction "2_2") (pintype "passive"))
      (node (ref "C106") (pin "2") (pinfunction "2_2") (pintype "passive"))
      (node (ref "C107") (pin "2") (pinfunction "2_2") (pintype "passive"))
      (node (ref "C108") (pin "2") (pinfunction "2_2") (pintype "passive"))
      (node (ref "C109") (pin "2") (pinfunction "2_2") (pintype "passive"))
      (node (ref "C110") (pin "2") (pinfunction "2_2") (pintype "passive"))
      (node (ref "C111") (pin "2") (pinfunction "2_2") (pintype "passive"))
      (node (ref "C113") (pin "1") (pinfunction "1_1") (pintype "passive"))
      (node (ref "J1") (pin "1") (pinfunction "P$1_1") (pintype "bidirectional"))
      (node (ref "J100") (pin "G1") (pinfunction "GND_G1") (pintype "passive"))
      (node (ref "J100") (pin "G2") (pinfunction "GND_G2") (pintype "passive"))
      (node (ref "J100") (pin "G3") (pinfunction "GND_G3") (pintype "passive"))
      (node (ref "J100") (pin "G4") (pinfunction "GND_G4") (pintype "passive"))
      (node (ref "J101") (pin "G1") (pinfunction "GND_G1") (pintype "passive"))
      (node (ref "J101") (pin "G2") (pinfunction "GND_G2") (pintype "passive"))
      (node (ref "J101") (pin "G3") (pinfunction "GND_G3") (pintype "passive"))
      (node (ref "J101") (pin "G4") (pinfunction "GND_G4") (pintype "passive"))
      (node (ref "J102") (pin "G1") (pinfunction "GND_G1") (pintype "passive"))
      (node (ref "J102") (pin "G2") (pinfunction "GND_G2") (pintype "passive"))
      (node (ref "J102") (pin "G3") (pinfunction "GND_G3") (pintype "passive"))
      (node (ref "J102") (pin "G4") (pinfunction "GND_G4") (pintype "passive"))
      (node (ref "J103") (pin "G1") (pinfunction "GND_G1") (pintype "passive"))
      (node (ref "J103") (pin "G2") (pinfunction "GND_G2") (pintype "passive"))
      (node (ref "J103") (pin "G3") (pinfunction "GND_G3") (pintype "passive"))
      (node (ref "J103") (pin "G4") (pinfunction "GND_G4") (pintype "passive"))
      (node (ref "J105") (pin "2") (pinfunction "P$3_2") (pintype "bidirectional"))
      (node (ref "JP101") (pin "2") (pinfunction "2_2") (pintype "passive"))
      (node (ref "JP102") (pin "1") (pinfunction "1_1") (pintype "passive"))
      (node (ref "JP102") (pin "2") (pinfunction "2_2") (pintype "passive"))
      (node (ref "JP102") (pin "3") (pinfunction "3_3") (pintype "passive"))
      (node (ref "JP102") (pin "4") (pinfunction "4_4") (pintype "passive"))
      (node (ref "JP103") (pin "2") (pinfunction "2_2") (pintype "passive"))
      (node (ref "JP104") (pin "2") (pinfunction "2_2") (pintype "passive"))
      (node (ref "JP105") (pin "2") (pinfunction "2_2") (pintype "passive"))
      (node (ref "JP106") (pin "2") (pinfunction "2_2") (pintype "passive"))
      (node (ref "M1A") (pin "19") (pinfunction "GND1_19") (pintype "bidirectional"))
      (node (ref "M1A") (pin "20") (pinfunction "GND2_20") (pintype "bidirectional"))
      (node (ref "M1B") (pin "1") (pinfunction "GND3_1") (pintype "bidirectional"))
      (node (ref "M1B") (pin "19") (pinfunction "GND5_19") (pintype "bidirectional"))
      (node (ref "M1B") (pin "2") (pinfunction "GND4_2") (pintype "bidirectional"))
      (node (ref "M1B") (pin "20") (pinfunction "GND6_20") (pintype "bidirectional"))
      (node (ref "M1B") (pin "31") (pinfunction "GND7_31") (pintype "bidirectional"))
      (node (ref "M1B") (pin "32") (pinfunction "GND8_32") (pintype "bidirectional"))
      (node (ref "M1B") (pin "49") (pinfunction "GND9_49") (pintype "bidirectional"))
      (node (ref "M1B") (pin "50") (pinfunction "GND10_50") (pintype "bidirectional"))
      (node (ref "M1C") (pin "1") (pinfunction "GND15_1") (pintype "bidirectional"))
      (node (ref "M1C") (pin "19") (pinfunction "GND17_19") (pintype "bidirectional"))
      (node (ref "M1C") (pin "2") (pinfunction "GND16_2") (pintype "bidirectional"))
      (node (ref "M1C") (pin "20") (pinfunction "GND18_20") (pintype "bidirectional"))
      (node (ref "M1C") (pin "31") (pinfunction "GND19_31") (pintype "bidirectional"))
      (node (ref "M1C") (pin "32") (pinfunction "GND20_32") (pintype "bidirectional"))
      (node (ref "M1C") (pin "49") (pinfunction "GND13_49") (pintype "bidirectional"))
      (node (ref "M1C") (pin "50") (pinfunction "GND14_50") (pintype "bidirectional"))
      (node (ref "P1") (pin "11") (pinfunction "11_11") (pintype "bidirectional"))
      (node (ref "P10") (pin "11") (pinfunction "11_11") (pintype "bidirectional"))
      (node (ref "P11") (pin "11") (pinfunction "11_11") (pintype "bidirectional"))
      (node (ref "P12") (pin "11") (pinfunction "11_11") (pintype "bidirectional"))
      (node (ref "P2") (pin "11") (pinfunction "11_11") (pintype "bidirectional"))
      (node (ref "P3") (pin "11") (pinfunction "11_11") (pintype "bidirectional"))
      (node (ref "P4") (pin "11") (pinfunction "11_11") (pintype "bidirectional"))
      (node (ref "P5") (pin "11") (pinfunction "11_11") (pintype "bidirectional"))
      (node (ref "P6") (pin "11") (pinfunction "11_11") (pintype "bidirectional"))
      (node (ref "P7") (pin "11") (pinfunction "11_11") (pintype "bidirectional"))
      (node (ref "P8") (pin "11") (pinfunction "11_11") (pintype "bidirectional"))
      (node (ref "P9") (pin "11") (pinfunction "11_11") (pintype "bidirectional"))
      (node (ref "R123") (pin "2") (pinfunction "2_2") (pintype "passive"))
      (node (ref "U100") (pin "2") (pinfunction "GND_2") (pintype "bidirectional"))
      (node (ref "U101") (pin "2") (pinfunction "GND_2") (pintype "bidirectional"))
      (node (ref "U102") (pin "14") (pinfunction "~{UB}_14") (pintype "bidirectional"))
      (node (ref "U102") (pin "15") (pinfunction "~{LB}_15") (pintype "bidirectional"))
      (node (ref "U102") (pin "26") (pinfunction "~{CE}_26") (pintype "bidirectional"))
      (node (ref "U102") (pin "27") (pinfunction "VSS_27") (pintype "bidirectional"))
      (node (ref "U102") (pin "46") (pinfunction "VSS2_46") (pintype "bidirectional"))
      (node (ref "U105") (pin "4") (pinfunction "DS2_4") (pintype "passive"))
      (node (ref "U106") (pin "2") (pinfunction "GND_2") (pintype "bidirectional"))
      (node (ref "U107") (pin "4") (pinfunction "GND_4") (pintype "input"))
      (node (ref "U108") (pin "2") (pinfunction "K_2") (pintype "passive"))
      (node (ref "U109") (pin "2") (pinfunction "GND_2") (pintype "bidirectional"))
    )
    (net (code "35") (name "DQ0") (class "Default")
      (node (ref "M1A") (pin "18") (pinfunction "C4_18") (pintype "bidirectional"))
      (node (ref "U102") (pin "29") (pinfunction "DQ0_29") (pintype "bidirectional"))
    )
    (net (code "36") (name "DQ1") (class "Default")
      (node (ref "M1A") (pin "16") (pinfunction "A3_16") (pintype "bidirectional"))
      (node (ref "U102") (pin "31") (pinfunction "DQ1_31") (pintype "bidirectional"))
    )
    (net (code "37") (name "DQ2") (class "Default")
      (node (ref "M1A") (pin "14") (pinfunction "B2_14") (pintype "bidirectional"))
      (node (ref "U102") (pin "33") (pinfunction "DQ2_33") (pintype "bidirectional"))
    )
    (net (code "38") (name "DQ3") (class "Default")
      (node (ref "M1A") (pin "12") (pinfunction "C2_12") (pintype "bidirectional"))
      (node (ref "U102") (pin "35") (pinfunction "DQ3_35") (pintype "bidirectional"))
    )
    (net (code "39") (name "DQ4") (class "Default")
      (node (ref "M1A") (pin "10") (pinfunction "D1_10") (pintype "bidirectional"))
      (node (ref "U102") (pin "38") (pinfunction "DQ4_38") (pintype "bidirectional"))
    )
    (net (code "40") (name "DQ5") (class "Default")
      (node (ref "M1A") (pin "8") (pinfunction "E1_8") (pintype "bidirectional"))
      (node (ref "U102") (pin "40") (pinfunction "DQ5_40") (pintype "bidirectional"))
    )
    (net (code "41") (name "DQ6") (class "Default")
      (node (ref "M1A") (pin "6") (pinfunction "G2_6") (pintype "bidirectional"))
      (node (ref "U102") (pin "42") (pinfunction "DQ6_42") (pintype "bidirectional"))
    )
    (net (code "42") (name "DQ7") (class "Default")
      (node (ref "M1A") (pin "4") (pinfunction "H2_4") (pintype "bidirectional"))
      (node (ref "U102") (pin "44") (pinfunction "DQ7_44") (pintype "bidirectional"))
    )
    (net (code "43") (name "DQ8") (class "Default")
      (node (ref "M1A") (pin "17") (pinfunction "D4_17") (pintype "bidirectional"))
      (node (ref "U102") (pin "30") (pinfunction "DQ8_30") (pintype "bidirectional"))
    )
    (net (code "44") (name "DQ9") (class "Default")
      (node (ref "M1A") (pin "15") (pinfunction "A2_15") (pintype "bidirectional"))
      (node (ref "U102") (pin "32") (pinfunction "DQ9_32") (pintype "bidirectional"))
    )
    (net (code "45") (name "DQ10") (class "Default")
      (node (ref "M1A") (pin "13") (pinfunction "B1_13") (pintype "bidirectional"))
      (node (ref "U102") (pin "34") (pinfunction "DQ10_34") (pintype "bidirectional"))
    )
    (net (code "46") (name "DQ11") (class "Default")
      (node (ref "M1A") (pin "11") (pinfunction "C1_11") (pintype "bidirectional"))
      (node (ref "U102") (pin "36") (pinfunction "DQ11_36") (pintype "bidirectional"))
    )
    (net (code "47") (name "DQ12") (class "Default")
      (node (ref "M1A") (pin "9") (pinfunction "E2_9") (pintype "bidirectional"))
      (node (ref "U102") (pin "39") (pinfunction "DQ12_39") (pintype "bidirectional"))
    )
    (net (code "48") (name "DQ13") (class "Default")
      (node (ref "M1A") (pin "7") (pinfunction "F2_7") (pintype "bidirectional"))
      (node (ref "U102") (pin "41") (pinfunction "DQ13_41") (pintype "bidirectional"))
    )
    (net (code "49") (name "DQ14") (class "Default")
      (node (ref "M1A") (pin "5") (pinfunction "G1_5") (pintype "bidirectional"))
      (node (ref "U102") (pin "43") (pinfunction "DQ14_43") (pintype "bidirectional"))
    )
    (net (code "50") (name "DQ15") (class "Default")
      (node (ref "M1A") (pin "3") (pinfunction "H1_3") (pintype "bidirectional"))
      (node (ref "U102") (pin "45") (pinfunction "DQ15_45") (pintype "bidirectional"))
    )
    (net (code "51") (name "LED1") (class "Default")
      (node (ref "J100") (pin "S") (pinfunction "1_S") (pintype "passive"))
      (node (ref "R122") (pin "1") (pinfunction "1_1") (pintype "passive"))
    )
    (net (code "52") (name "LED1_INV") (class "Default")
      (node (ref "JP106") (pin "1") (pinfunction "1_1") (pintype "passive"))
      (node (ref "M1B") (pin "27") (pinfunction "T2_27") (pintype "bidirectional"))
      (node (ref "R127") (pin "2") (pinfunction "2_2") (pintype "passive"))
    )
    (net (code "53") (name "LED2") (class "Default")
      (node (ref "J102") (pin "S") (pinfunction "1_S") (pintype "passive"))
      (node (ref "R121") (pin "1") (pinfunction "1_1") (pintype "passive"))
    )
    (net (code "54") (name "LED2_INV") (class "Default")
      (node (ref "JP105") (pin "1") (pinfunction "1_1") (pintype "passive"))
      (node (ref "M1B") (pin "25") (pinfunction "R2_25") (pintype "bidirectional"))
      (node (ref "R124") (pin "2") (pinfunction "2_2") (pintype "passive"))
    )
    (net (code "55") (name "MISO1") (class "Default")
      (node (ref "M1C") (pin "34") (pinfunction "D14_34") (pintype "bidirectional"))
      (node (ref "R103") (pin "2") (pinfunction "2_2") (pintype "passive"))
    )
    (net (code "56") (name "MISO1R") (class "Default")
      (node (ref "P1") (pin "2") (pinfunction "2_2") (pintype "bidirectional"))
      (node (ref "R103") (pin "1") (pinfunction "1_1") (pintype "passive"))
    )
    (net (code "57") (name "MISO2") (class "Default")
      (node (ref "M1C") (pin "33") (pinfunction "D16_33") (pintype "bidirectional"))
      (node (ref "R102") (pin "2") (pinfunction "2_2") (pintype "passive"))
    )
    (net (code "58") (name "MISO3") (class "Default")
      (node (ref "M1C") (pin "36") (pinfunction "E15_36") (pintype "bidirectional"))
      (node (ref "R112") (pin "2") (pinfunction "2_2") (pintype "passive"))
    )
    (net (code "59") (name "MISO4") (class "Default")
      (node (ref "M1C") (pin "35") (pinfunction "E16_35") (pintype "bidirectional"))
      (node (ref "R113") (pin "2") (pinfunction "2_2") (pintype "passive"))
    )
    (net (code "60") (name "MISO5") (class "Default")
      (node (ref "M1C") (pin "38") (pinfunction "F14_38") (pintype "bidirectional"))
      (node (ref "R111") (pin "2") (pinfunction "2_2") (pintype "passive"))
    )
    (net (code "61") (name "MISO6") (class "Default")
      (node (ref "M1C") (pin "37") (pinfunction "G15_37") (pintype "bidirectional"))
      (node (ref "R109") (pin "2") (pinfunction "2_2") (pintype "passive"))
    )
    (net (code "62") (name "MISO7") (class "Default")
      (node (ref "M1C") (pin "40") (pinfunction "G16_40") (pintype "bidirectional"))
      (node (ref "R110") (pin "2") (pinfunction "2_2") (pintype "passive"))
    )
    (net (code "63") (name "MISO8") (class "Default")
      (node (ref "M1C") (pin "39") (pinfunction "H14_39") (pintype "bidirectional"))
      (node (ref "R108") (pin "2") (pinfunction "2_2") (pintype "passive"))
    )
    (net (code "64") (name "MISO9") (class "Default")
      (node (ref "M1C") (pin "44") (pinfunction "H16_44") (pintype "bidirectional"))
      (node (ref "R107") (pin "2") (pinfunction "2_2") (pintype "passive"))
    )
    (net (code "65") (name "MISO10") (class "Default")
      (node (ref "M1C") (pin "43") (pinfunction "H13_43") (pintype "bidirectional"))
      (node (ref "R104") (pin "2") (pinfunction "2_2") (pintype "passive"))
    )
    (net (code "66") (name "MISO11") (class "Default")
      (node (ref "M1C") (pin "46") (pinfunction "G14_46") (pintype "bidirectional"))
      (node (ref "R106") (pin "2") (pinfunction "2_2") (pintype "passive"))
    )
    (net (code "67") (name "MISO12") (class "Default")
      (node (ref "M1C") (pin "45") (pinfunction "F15_45") (pintype "bidirectional"))
      (node (ref "R105") (pin "2") (pinfunction "2_2") (pintype "passive"))
    )
    (net (code "68") (name "MOSI") (class "Default")
      (node (ref "P1") (pin "1") (pinfunction "1_1") (pintype "bidirectional"))
      (node (ref "P10") (pin "1") (pinfunction "1_1") (pintype "bidirectional"))
      (node (ref "P11") (pin "1") (pinfunction "1_1") (pintype "bidirectional"))
      (node (ref "P12") (pin "1") (pinfunction "1_1") (pintype "bidirectional"))
      (node (ref "P2") (pin "1") (pinfunction "1_1") (pintype "bidirectional"))
      (node (ref "P3") (pin "1") (pinfunction "1_1") (pintype "bidirectional"))
      (node (ref "P4") (pin "1") (pinfunction "1_1") (pintype "bidirectional"))
      (node (ref "P5") (pin "1") (pinfunction "1_1") (pintype "bidirectional"))
      (node (ref "P6") (pin "1") (pinfunction "1_1") (pintype "bidirectional"))
      (node (ref "P7") (pin "1") (pinfunction "1_1") (pintype "bidirectional"))
      (node (ref "P8") (pin "1") (pinfunction "1_1") (pintype "bidirectional"))
      (node (ref "P9") (pin "1") (pinfunction "1_1") (pintype "bidirectional"))
      (node (ref "R100") (pin "2") (pinfunction "2_2") (pintype "passive"))
    )
    (net (code "69") (name "MOSIR") (class "Default")
      (node (ref "R100") (pin "1") (pinfunction "1_1") (pintype "passive"))
      (node (ref "U100") (pin "4") (pinfunction "2Y_4") (pintype "bidirectional"))
    )
    (net (code "70") (name "N$16") (class "Default")
      (node (ref "M1B") (pin "28") (pinfunction "R3_28") (pintype "bidirectional"))
      (node (ref "U106") (pin "3") (pinfunction "2A_3") (pintype "bidirectional"))
    )
    (net (code "71") (name "Net-(M1B-K3)") (class "Default")
      (node (ref "M1B") (pin "12") (pinfunction "K3_12") (pintype "bidirectional"))
      (node (ref "U105") (pin "3") (pinfunction "DS1_3") (pintype "passive"))
    )
    (net (code "72") (name "Net-(M1B-M1)") (class "Default")
      (node (ref "M1B") (pin "14") (pinfunction "M1_14") (pintype "bidirectional"))
      (node (ref "R115") (pin "1") (pinfunction "1_1") (pintype "passive"))
    )
    (net (code "73") (name "Net-(P2-Pad2)") (class "Default")
      (node (ref "P2") (pin "2") (pinfunction "2_2") (pintype "bidirectional"))
      (node (ref "R102") (pin "1") (pinfunction "1_1") (pintype "passive"))
    )
    (net (code "74") (name "Net-(P3-Pad2)") (class "Default")
      (node (ref "P3") (pin "2") (pinfunction "2_2") (pintype "bidirectional"))
      (node (ref "R112") (pin "1") (pinfunction "1_1") (pintype "passive"))
    )
    (net (code "75") (name "Net-(P4-Pad2)") (class "Default")
      (node (ref "P4") (pin "2") (pinfunction "2_2") (pintype "bidirectional"))
      (node (ref "R113") (pin "1") (pinfunction "1_1") (pintype "passive"))
    )
    (net (code "76") (name "Net-(P5-Pad2)") (class "Default")
      (node (ref "P5") (pin "2") (pinfunction "2_2") (pintype "bidirectional"))
      (node (ref "R111") (pin "1") (pinfunction "1_1") (pintype "passive"))
    )
    (net (code "77") (name "Net-(P6-Pad2)") (class "Default")
      (node (ref "P6") (pin "2") (pinfunction "2_2") (pintype "bidirectional"))
      (node (ref "R109") (pin "1") (pinfunction "1_1") (pintype "passive"))
    )
    (net (code "78") (name "Net-(P7-Pad2)") (class "Default")
      (node (ref "P7") (pin "2") (pinfunction "2_2") (pintype "bidirectional"))
      (node (ref "R110") (pin "1") (pinfunction "1_1") (pintype "passive"))
    )
    (net (code "79") (name "Net-(P8-Pad2)") (class "Default")
      (node (ref "P8") (pin "2") (pinfunction "2_2") (pintype "bidirectional"))
      (node (ref "R108") (pin "1") (pinfunction "1_1") (pintype "passive"))
    )
    (net (code "80") (name "Net-(P9-Pad2)") (class "Default")
      (node (ref "P9") (pin "2") (pinfunction "2_2") (pintype "bidirectional"))
      (node (ref "R107") (pin "1") (pinfunction "1_1") (pintype "passive"))
    )
    (net (code "81") (name "Net-(P10-Pad2)") (class "Default")
      (node (ref "P10") (pin "2") (pinfunction "2_2") (pintype "bidirectional"))
      (node (ref "R104") (pin "1") (pinfunction "1_1") (pintype "passive"))
    )
    (net (code "82") (name "Net-(P11-Pad2)") (class "Default")
      (node (ref "P11") (pin "2") (pinfunction "2_2") (pintype "bidirectional"))
      (node (ref "R106") (pin "1") (pinfunction "1_1") (pintype "passive"))
    )
    (net (code "83") (name "Net-(P12-Pad2)") (class "Default")
      (node (ref "P12") (pin "2") (pinfunction "2_2") (pintype "bidirectional"))
      (node (ref "R105") (pin "1") (pinfunction "1_1") (pintype "passive"))
    )
    (net (code "84") (name "Net-(U103-NC{slash}FB)") (class "Default")
      (node (ref "C102") (pin "1") (pinfunction "1_1") (pintype "passive"))
      (node (ref "U103") (pin "4") (pinfunction "NC/FB_4") (pintype "passive"))
    )
    (net (code "85") (name "Net-(U104-+)") (class "Default")
      (node (ref "R119") (pin "1") (pinfunction "1_1") (pintype "passive"))
      (node (ref "R120") (pin "2") (pinfunction "2_2") (pintype "passive"))
      (node (ref "U104") (pin "3") (pinfunction "+_3") (pintype "bidirectional"))
    )
    (net (code "86") (name "Net-(U104--)") (class "Default")
      (node (ref "U104") (pin "4") (pinfunction "-_4") (pintype "bidirectional"))
      (node (ref "U104") (pin "5") (pinfunction "HY_5") (pintype "bidirectional"))
      (node (ref "U104") (pin "6") (pinfunction "1.182_6") (pintype "bidirectional"))
    )
    (net (code "87") (name "Net-(U104-OUT)") (class "Default")
      (node (ref "R117") (pin "1") (pinfunction "1_1") (pintype "passive"))
      (node (ref "U104") (pin "8") (pinfunction "OUT_8") (pintype "bidirectional"))
    )
    (net (code "88") (name "Net-(U105-A)") (class "Default")
      (node (ref "R117") (pin "2") (pinfunction "2_2") (pintype "passive"))
      (node (ref "U105") (pin "1") (pinfunction "A_1") (pintype "passive"))
    )
    (net (code "89") (name "Net-(U106-1Y)") (class "Default")
      (node (ref "R116") (pin "1") (pinfunction "1_1") (pintype "passive"))
      (node (ref "U106") (pin "6") (pinfunction "1Y_6") (pintype "bidirectional"))
    )
    (net (code "90") (name "Net-(U106-2Y)") (class "Default")
      (node (ref "R118") (pin "1") (pinfunction "1_1") (pintype "passive"))
      (node (ref "U106") (pin "4") (pinfunction "2Y_4") (pintype "bidirectional"))
    )
    (net (code "91") (name "Net-(U108-A)") (class "Default")
      (node (ref "R115") (pin "2") (pinfunction "2_2") (pintype "passive"))
      (node (ref "U108") (pin "1") (pinfunction "A_1") (pintype "passive"))
    )
    (net (code "92") (name "Net-(U109-1Y)") (class "Default")
      (node (ref "R121") (pin "2") (pinfunction "2_2") (pintype "passive"))
      (node (ref "U109") (pin "6") (pinfunction "1Y_6") (pintype "bidirectional"))
    )
    (net (code "93") (name "Net-(U109-2Y)") (class "Default")
      (node (ref "R122") (pin "2") (pinfunction "2_2") (pintype "passive"))
      (node (ref "U109") (pin "4") (pinfunction "2Y_4") (pintype "bidirectional"))
    )
    (net (code "94") (name "OE#") (class "Default")
      (node (ref "M1B") (pin "4") (pinfunction "P10_4") (pintype "bidirectional"))
      (node (ref "U102") (pin "28") (pinfunction "~{OE}_28") (pintype "bidirectional"))
    )
    (net (code "95") (name "SERIAL") (class "Default")
      (node (ref "M1B") (pin "15") (pinfunction "M2_15") (pintype "bidirectional"))
      (node (ref "U101") (pin "3") (pinfunction "2A_3") (pintype "bidirectional"))
    )
    (net (code "96") (name "SERIALOUT") (class "Default")
      (node (ref "J1") (pin "2") (pinfunction "P$2_2") (pintype "bidirectional"))
      (node (ref "U101") (pin "4") (pinfunction "2Y_4") (pintype "bidirectional"))
    )
    (net (code "97") (name "SYNC") (class "Default")
      (node (ref "J101") (pin "S") (pinfunction "1_S") (pintype "passive"))
      (node (ref "R118") (pin "2") (pinfunction "2_2") (pintype "passive"))
    )
    (net (code "98") (name "SYNC_INV") (class "Default")
      (node (ref "JP103") (pin "1") (pinfunction "1_1") (pintype "passive"))
      (node (ref "M1B") (pin "23") (pinfunction "P1_23") (pintype "bidirectional"))
      (node (ref "R125") (pin "2") (pinfunction "2_2") (pintype "passive"))
    )
    (net (code "99") (name "TEN") (class "Default")
      (node (ref "M1B") (pin "7") (pinfunction "K2_7") (pintype "bidirectional"))
      (node (ref "P1") (pin "7") (pinfunction "7_7") (pintype "bidirectional"))
      (node (ref "P10") (pin "7") (pinfunction "7_7") (pintype "bidirectional"))
      (node (ref "P11") (pin "7") (pinfunction "7_7") (pintype "bidirectional"))
      (node (ref "P12") (pin "7") (pinfunction "7_7") (pintype "bidirectional"))
      (node (ref "P2") (pin "7") (pinfunction "7_7") (pintype "bidirectional"))
      (node (ref "P3") (pin "7") (pinfunction "7_7") (pintype "bidirectional"))
      (node (ref "P4") (pin "7") (pinfunction "7_7") (pintype "bidirectional"))
      (node (ref "P5") (pin "7") (pinfunction "7_7") (pintype "bidirectional"))
      (node (ref "P6") (pin "7") (pinfunction "7_7") (pintype "bidirectional"))
      (node (ref "P7") (pin "7") (pinfunction "7_7") (pintype "bidirectional"))
      (node (ref "P8") (pin "7") (pinfunction "7_7") (pintype "bidirectional"))
      (node (ref "P9") (pin "7") (pinfunction "7_7") (pintype "bidirectional"))
    )
    (net (code "100") (name "TMI1") (class "Default")
      (node (ref "M1B") (pin "8") (pinfunction "K1_8") (pintype "bidirectional"))
      (node (ref "P1") (pin "5") (pinfunction "5_5") (pintype "bidirectional"))
    )
    (net (code "101") (name "TMO1") (class "Default")
      (node (ref "P1") (pin "6") (pinfunction "6_6") (pintype "bidirectional"))
      (node (ref "P2") (pin "5") (pinfunction "5_5") (pintype "bidirectional"))
    )
    (net (code "102") (name "TMO2") (class "Default")
      (node (ref "P2") (pin "6") (pinfunction "6_6") (pintype "bidirectional"))
      (node (ref "P3") (pin "5") (pinfunction "5_5") (pintype "bidirectional"))
    )
    (net (code "103") (name "TMO3") (class "Default")
      (node (ref "P3") (pin "6") (pinfunction "6_6") (pintype "bidirectional"))
      (node (ref "P4") (pin "5") (pinfunction "5_5") (pintype "bidirectional"))
    )
    (net (code "104") (name "TMO4") (class "Default")
      (node (ref "P4") (pin "6") (pinfunction "6_6") (pintype "bidirectional"))
      (node (ref "P5") (pin "5") (pinfunction "5_5") (pintype "bidirectional"))
    )
    (net (code "105") (name "TMO5") (class "Default")
      (node (ref "P5") (pin "6") (pinfunction "6_6") (pintype "bidirectional"))
      (node (ref "P6") (pin "5") (pinfunction "5_5") (pintype "bidirectional"))
    )
    (net (code "106") (name "TMO6") (class "Default")
      (node (ref "P6") (pin "6") (pinfunction "6_6") (pintype "bidirectional"))
      (node (ref "P7") (pin "5") (pinfunction "5_5") (pintype "bidirectional"))
    )
    (net (code "107") (name "TMO7") (class "Default")
      (node (ref "P7") (pin "6") (pinfunction "6_6") (pintype "bidirectional"))
      (node (ref "P8") (pin "5") (pinfunction "5_5") (pintype "bidirectional"))
    )
    (net (code "108") (name "TMO8") (class "Default")
      (node (ref "P8") (pin "6") (pinfunction "6_6") (pintype "bidirectional"))
      (node (ref "P9") (pin "5") (pinfunction "5_5") (pintype "bidirectional"))
    )
    (net (code "109") (name "TMO9") (class "Default")
      (node (ref "P10") (pin "5") (pinfunction "5_5") (pintype "bidirectional"))
      (node (ref "P9") (pin "6") (pinfunction "6_6") (pintype "bidirectional"))
    )
    (net (code "110") (name "TMO10") (class "Default")
      (node (ref "P10") (pin "6") (pinfunction "6_6") (pintype "bidirectional"))
      (node (ref "P11") (pin "5") (pinfunction "5_5") (pintype "bidirectional"))
    )
    (net (code "111") (name "TMO11") (class "Default")
      (node (ref "P11") (pin "6") (pinfunction "6_6") (pintype "bidirectional"))
      (node (ref "P12") (pin "5") (pinfunction "5_5") (pintype "bidirectional"))
    )
    (net (code "112") (name "TMO12") (class "Default")
      (node (ref "M1C") (pin "47") (pinfunction "E12_47") (pintype "bidirectional"))
      (node (ref "P12") (pin "6") (pinfunction "6_6") (pintype "bidirectional"))
    )
    (net (code "113") (name "TP0") (class "Default")
      (node (ref "M1B") (pin "48") (pinfunction "T10_48") (pintype "bidirectional"))
    )
    (net (code "114") (name "TP1") (class "Default")
      (node (ref "M1B") (pin "47") (pinfunction "T8_47") (pintype "bidirectional"))
    )
    (net (code "115") (name "TP2") (class "Default")
      (node (ref "M1B") (pin "46") (pinfunction "R8_46") (pintype "bidirectional"))
    )
    (net (code "116") (name "TP3") (class "Default")
      (node (ref "M1B") (pin "45") (pinfunction "T7_45") (pintype "bidirectional"))
    )
    (net (code "117") (name "TP4") (class "Default")
      (node (ref "M1B") (pin "44") (pinfunction "R7_44") (pintype "bidirectional"))
    )
    (net (code "118") (name "TP5") (class "Default")
      (node (ref "M1B") (pin "43") (pinfunction "T9_43") (pintype "bidirectional"))
    )
    (net (code "119") (name "TP6") (class "Default")
      (node (ref "M1B") (pin "40") (pinfunction "R6_40") (pintype "bidirectional"))
    )
    (net (code "120") (name "TP7") (class "Default")
      (node (ref "M1B") (pin "39") (pinfunction "T5_39") (pintype "bidirectional"))
    )
    (net (code "121") (name "TP8") (class "Default")
      (node (ref "M1B") (pin "38") (pinfunction "P8_38") (pintype "bidirectional"))
    )
    (net (code "122") (name "TP9") (class "Default")
      (node (ref "M1B") (pin "37") (pinfunction "R5_37") (pintype "bidirectional"))
    )
    (net (code "123") (name "TP10") (class "Default")
      (node (ref "M1B") (pin "36") (pinfunction "N6_36") (pintype "bidirectional"))
    )
    (net (code "124") (name "TP11") (class "Default")
      (node (ref "M1B") (pin "35") (pinfunction "P5_35") (pintype "bidirectional"))
    )
    (net (code "125") (name "TP12") (class "Default")
      (node (ref "M1B") (pin "34") (pinfunction "T4_34") (pintype "bidirectional"))
    )
    (net (code "126") (name "TP13") (class "Default")
      (node (ref "M1B") (pin "33") (pinfunction "P4_33") (pintype "bidirectional"))
    )
    (net (code "127") (name "TP14") (class "Default")
      (node (ref "M1B") (pin "30") (pinfunction "N4_30") (pintype "bidirectional"))
    )
    (net (code "128") (name "TP15") (class "Default")
      (node (ref "M1B") (pin "29") (pinfunction "T3_29") (pintype "bidirectional"))
    )
    (net (code "129") (name "UCLK") (class "Default")
      (node (ref "M1C") (pin "27") (pinfunction "B15_27") (pintype "bidirectional"))
      (node (ref "U101") (pin "1") (pinfunction "1A_1") (pintype "bidirectional"))
    )
    (net (code "130") (name "UCS") (class "Default")
      (node (ref "M1C") (pin "30") (pinfunction "D15_30") (pintype "bidirectional"))
      (node (ref "U100") (pin "1") (pinfunction "1A_1") (pintype "bidirectional"))
    )
    (net (code "131") (name "ULED1") (class "Default")
      (node (ref "M1B") (pin "11") (pinfunction "L2_11") (pintype "bidirectional"))
      (node (ref "U109") (pin "3") (pinfunction "2A_3") (pintype "bidirectional"))
    )
    (net (code "132") (name "ULED2") (class "Default")
      (node (ref "M1B") (pin "13") (pinfunction "L3_13") (pintype "bidirectional"))
      (node (ref "U109") (pin "1") (pinfunction "1A_1") (pintype "bidirectional"))
    )
    (net (code "133") (name "UMOSI") (class "Default")
      (node (ref "M1C") (pin "29") (pinfunction "C16_29") (pintype "bidirectional"))
      (node (ref "U100") (pin "3") (pinfunction "2A_3") (pintype "bidirectional"))
    )
    (net (code "134") (name "VIN") (class "Default")
      (node (ref "C109") (pin "1") (pinfunction "1_1") (pintype "passive"))
      (node (ref "C110") (pin "1") (pinfunction "1_1") (pintype "passive"))
      (node (ref "J105") (pin "1A") (pinfunction "P$1_1A") (pintype "bidirectional"))
      (node (ref "J105") (pin "1B") (pinfunction "P$1_1B") (pintype "bidirectional"))
      (node (ref "U107") (pin "1") (pinfunction "IN_1") (pintype "input"))
    )
    (net (code "135") (name "WE#") (class "Default")
      (node (ref "M1C") (pin "13") (pinfunction "B10_13") (pintype "bidirectional"))
      (node (ref "U102") (pin "11") (pinfunction "~{WE}_11") (pintype "bidirectional"))
    )
    (net (code "136") (name "unconnected-(J104-P$2-Pad2)") (class "Default")
      (node (ref "J104") (pin "2") (pinfunction "P$2_2") (pintype "bidirectional"))
    )
    (net (code "137") (name "unconnected-(J105-P$2-Pad3)") (class "Default")
      (node (ref "J105") (pin "3") (pinfunction "P$2_3") (pintype "bidirectional"))
    )
    (net (code "138") (name "unconnected-(M1B-+3V3_3-Pad9)") (class "Default")
      (node (ref "M1B") (pin "9") (pinfunction "+3V3_3_9") (pintype "bidirectional"))
    )
    (net (code "139") (name "unconnected-(M1B-+3V3_4-Pad10)") (class "Default")
      (node (ref "M1B") (pin "10") (pinfunction "+3V3_4_10") (pintype "bidirectional"))
    )
    (net (code "140") (name "unconnected-(M1B-CLK5-Pad3)") (class "Default")
      (node (ref "M1B") (pin "3") (pinfunction "CLK5_3") (pintype "bidirectional"))
    )
    (net (code "141") (name "unconnected-(M1B-L4-Pad16)") (class "Default")
      (node (ref "M1B") (pin "16") (pinfunction "L4_16") (pintype "bidirectional"))
    )
    (net (code "142") (name "unconnected-(M1B-M4-Pad17)") (class "Default")
      (node (ref "M1B") (pin "17") (pinfunction "M4_17") (pintype "bidirectional"))
    )
    (net (code "143") (name "unconnected-(M1B-N1-Pad18)") (class "Default")
      (node (ref "M1B") (pin "18") (pinfunction "N1_18") (pintype "bidirectional"))
    )
    (net (code "144") (name "unconnected-(M1B-N3-Pad22)") (class "Default")
      (node (ref "M1B") (pin "22") (pinfunction "N3_22") (pintype "bidirectional"))
    )
    (net (code "145") (name "unconnected-(M1B-R1-Pad24)") (class "Default")
      (node (ref "M1B") (pin "24") (pinfunction "R1_24") (pintype "bidirectional"))
    )
    (net (code "146") (name "unconnected-(M1C-+3V3_7-Pad9)") (class "Default")
      (node (ref "M1C") (pin "9") (pinfunction "+3V3_7_9") (pintype "bidirectional"))
    )
    (net (code "147") (name "unconnected-(M1C-+3V3_8-Pad10)") (class "Default")
      (node (ref "M1C") (pin "10") (pinfunction "+3V3_8_10") (pintype "bidirectional"))
    )
    (net (code "148") (name "unconnected-(M1C-+3V3_9-Pad41)") (class "Default")
      (node (ref "M1C") (pin "41") (pinfunction "+3V3_9_41") (pintype "bidirectional"))
    )
    (net (code "149") (name "unconnected-(M1C-+3V3_10-Pad42)") (class "Default")
      (node (ref "M1C") (pin "42") (pinfunction "+3V3_10_42") (pintype "bidirectional"))
    )
    (net (code "150") (name "unconnected-(M1C-CLK4-Pad48)") (class "Default")
      (node (ref "M1C") (pin "48") (pinfunction "CLK4_48") (pintype "bidirectional"))
    )
    (net (code "151") (name "unconnected-(P1-Pad8)") (class "Default")
      (node (ref "P1") (pin "8") (pinfunction "8_8") (pintype "bidirectional"))
    )
    (net (code "152") (name "unconnected-(P2-Pad8)") (class "Default")
      (node (ref "P2") (pin "8") (pinfunction "8_8") (pintype "bidirectional"))
    )
    (net (code "153") (name "unconnected-(P3-Pad8)") (class "Default")
      (node (ref "P3") (pin "8") (pinfunction "8_8") (pintype "bidirectional"))
    )
    (net (code "154") (name "unconnected-(P4-Pad8)") (class "Default")
      (node (ref "P4") (pin "8") (pinfunction "8_8") (pintype "bidirectional"))
    )
    (net (code "155") (name "unconnected-(P5-Pad8)") (class "Default")
      (node (ref "P5") (pin "8") (pinfunction "8_8") (pintype "bidirectional"))
    )
    (net (code "156") (name "unconnected-(P6-Pad8)") (class "Default")
      (node (ref "P6") (pin "8") (pinfunction "8_8") (pintype "bidirectional"))
    )
    (net (code "157") (name "unconnected-(P7-Pad8)") (class "Default")
      (node (ref "P7") (pin "8") (pinfunction "8_8") (pintype "bidirectional"))
    )
    (net (code "158") (name "unconnected-(P8-Pad8)") (class "Default")
      (node (ref "P8") (pin "8") (pinfunction "8_8") (pintype "bidirectional"))
    )
    (net (code "159") (name "unconnected-(P9-Pad8)") (class "Default")
      (node (ref "P9") (pin "8") (pinfunction "8_8") (pintype "bidirectional"))
    )
    (net (code "160") (name "unconnected-(P10-Pad8)") (class "Default")
      (node (ref "P10") (pin "8") (pinfunction "8_8") (pintype "bidirectional"))
    )
    (net (code "161") (name "unconnected-(P11-Pad8)") (class "Default")
      (node (ref "P11") (pin "8") (pinfunction "8_8") (pintype "bidirectional"))
    )
    (net (code "162") (name "unconnected-(P12-Pad8)") (class "Default")
      (node (ref "P12") (pin "8") (pinfunction "8_8") (pintype "bidirectional"))
    )
    (net (code "163") (name "~{CSR}") (class "Default")
      (node (ref "R101") (pin "1") (pinfunction "1_1") (pintype "passive"))
      (node (ref "U100") (pin "6") (pinfunction "1Y_6") (pintype "bidirectional"))
    )
    (net (code "164") (name "~{CS}") (class "Default")
      (node (ref "P1") (pin "4") (pinfunction "4_4") (pintype "bidirectional"))
      (node (ref "P10") (pin "4") (pinfunction "4_4") (pintype "bidirectional"))
      (node (ref "P11") (pin "4") (pinfunction "4_4") (pintype "bidirectional"))
      (node (ref "P12") (pin "4") (pinfunction "4_4") (pintype "bidirectional"))
      (node (ref "P2") (pin "4") (pinfunction "4_4") (pintype "bidirectional"))
      (node (ref "P3") (pin "4") (pinfunction "4_4") (pintype "bidirectional"))
      (node (ref "P4") (pin "4") (pinfunction "4_4") (pintype "bidirectional"))
      (node (ref "P5") (pin "4") (pinfunction "4_4") (pintype "bidirectional"))
      (node (ref "P6") (pin "4") (pinfunction "4_4") (pintype "bidirectional"))
      (node (ref "P7") (pin "4") (pinfunction "4_4") (pintype "bidirectional"))
      (node (ref "P8") (pin "4") (pinfunction "4_4") (pintype "bidirectional"))
      (node (ref "P9") (pin "4") (pinfunction "4_4") (pintype "bidirectional"))
      (node (ref "R101") (pin "2") (pinfunction "2_2") (pintype "passive"))
    )
  )
)
